# nano_shield.net
KiCad netlist of a schematic drawn in EAGLE
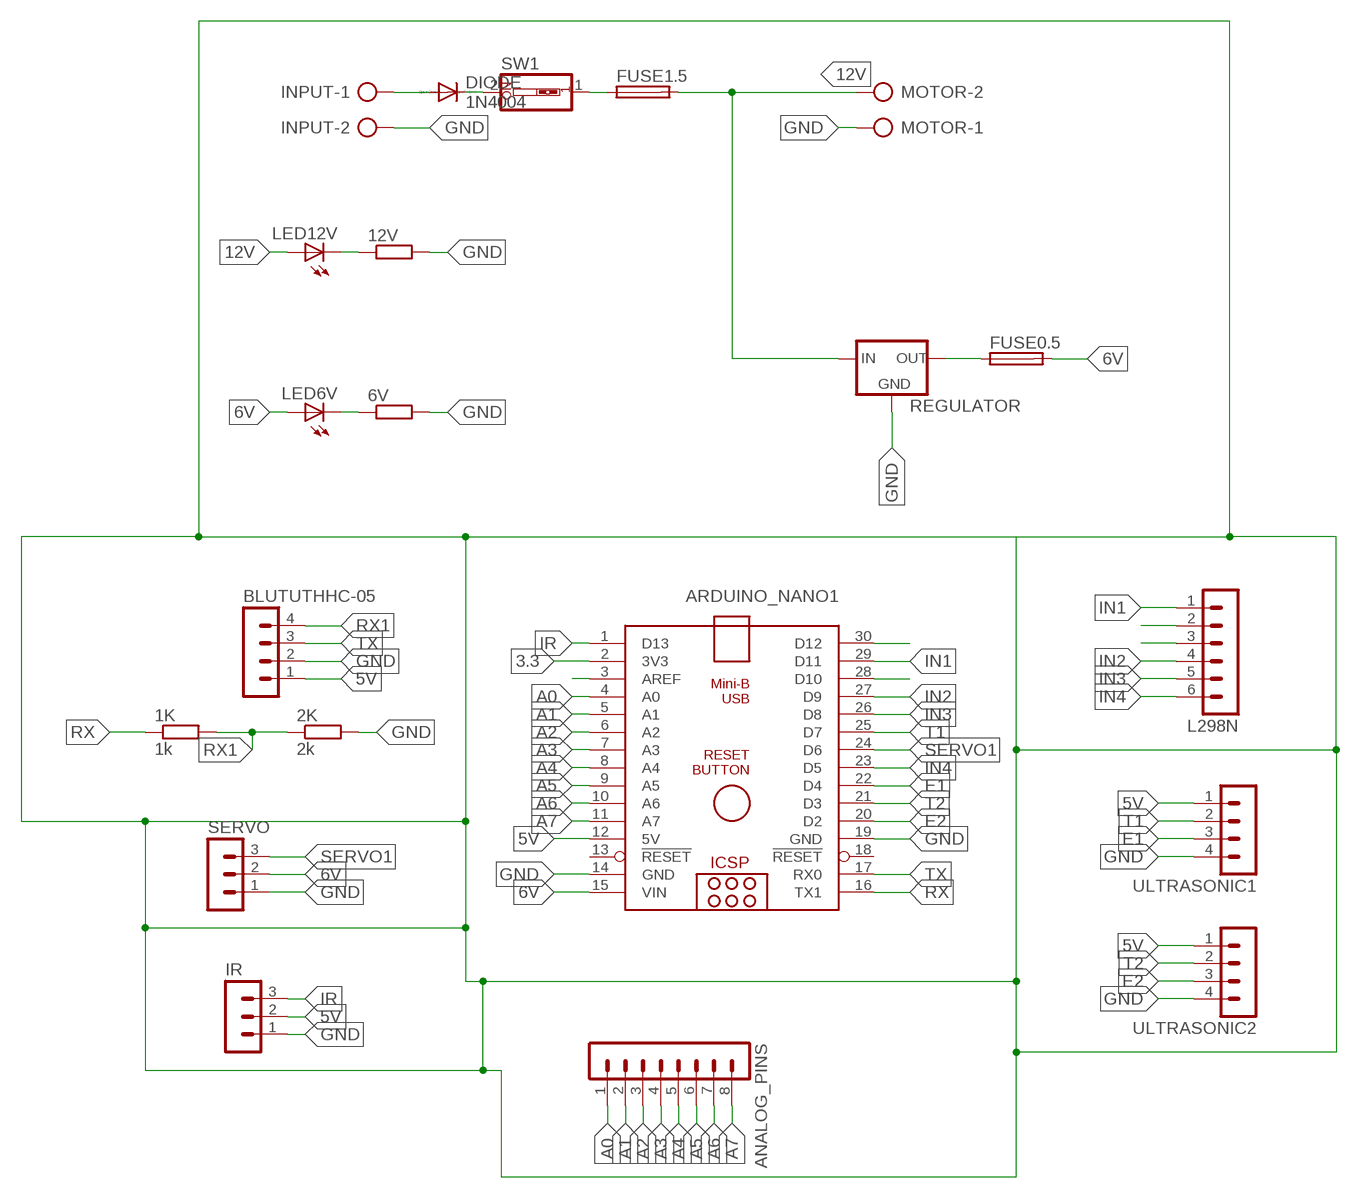
[diagram p0: schematic, sheet 1]

(export (version "E")
  (design (tool "Eeschema 10.0.6"))
  (components
    (comp (ref "1K")
      (value "1k")
      (footprint "eagle-import:0207_10")
      (libsource (lib "eagle-import") (part "R-EU_0207/10"))
    )
    (comp (ref "2K")
      (value "2k")
      (footprint "eagle-import:0207_10")
      (libsource (lib "eagle-import") (part "R-EU_0207/10"))
    )
    (comp (ref "6V")
      (value "R-EU_0204/7")
      (footprint "eagle-import:0204_7")
      (libsource (lib "eagle-import") (part "resistor_348_R-EU_0204/7"))
    )
    (comp (ref "12V")
      (value "R-EU_0204/7")
      (footprint "eagle-import:0204_7")
      (libsource (lib "eagle-import") (part "resistor_348_R-EU_0204/7"))
    )
    (comp (ref "ANALOG_PINS")
      (value "MA08-1")
      (footprint "eagle-import:MA08-1")
      (libsource (lib "eagle-import") (part "MA08-1"))
    )
    (comp (ref "ARDUINO_NANO1")
      (value "ARDUINO_NANO")
      (footprint "eagle-import:ARDUINO_NANO")
      (libsource (lib "eagle-import") (part "ARDUINO_NANO"))
    )
    (comp (ref "BLUTUTHHC-05")
      (value "MA04-1")
      (footprint "eagle-import:MA04-1")
      (libsource (lib "eagle-import") (part "MA04-1"))
    )
    (comp (ref "DIODE")
      (value "1N4004")
      (footprint "eagle-import:DO41-10")
      (libsource (lib "eagle-import") (part "1N4004"))
    )
    (comp (ref "FUSE0.5")
      (value "SH22,5")
      (footprint "eagle-import:SH22,5")
      (fields (field (name "MF") "SCHURTER") (field (name "MPN") "0031.8201"))
      (libsource (lib "eagle-import") (part "SH22,5"))
    )
    (comp (ref "FUSE1.5")
      (value "SH22,5")
      (footprint "eagle-import:SH22,5")
      (fields (field (name "MF") "SCHURTER") (field (name "MPN") "0031.8201"))
      (libsource (lib "eagle-import") (part "SH22,5"))
    )
    (comp (ref "INPUT")
      (value "AK500/2-H")
      (footprint "eagle-import:AK500_2-H")
      (libsource (lib "eagle-import") (part "AK500/2-H"))
    )
    (comp (ref "IR")
      (value "MA03-1")
      (footprint "eagle-import:MA03-1")
      (libsource (lib "eagle-import") (part "MA03-1"))
    )
    (comp (ref "L298N")
      (value "MA06-1")
      (footprint "eagle-import:MA06-1")
      (libsource (lib "eagle-import") (part "MA06-1"))
    )
    (comp (ref "LED6V")
      (value "LEDLSU260")
      (footprint "eagle-import:LSU260")
      (libsource (lib "eagle-import") (part "LEDLSU260"))
    )
    (comp (ref "LED12V")
      (value "LEDLSU260")
      (footprint "eagle-import:LSU260")
      (libsource (lib "eagle-import") (part "LEDLSU260"))
    )
    (comp (ref "MOTOR")
      (value "AK500/2-H")
      (footprint "eagle-import:AK500_2-H")
      (libsource (lib "eagle-import") (part "AK500/2-H"))
    )
    (comp (ref "REGULATOR")
      (value "78XXS")
      (footprint "eagle-import:78XXS")
      (libsource (lib "eagle-import") (part "78XXS"))
    )
    (comp (ref "SERVO")
      (value "MA03-1")
      (footprint "eagle-import:MA03-1")
      (libsource (lib "eagle-import") (part "MA03-1"))
    )
    (comp (ref "SW1")
      (value "SW_DIP-1")
      (footprint "eagle-import:EDG-01")
      (libsource (lib "eagle-import") (part "SW_DIP-1"))
    )
    (comp (ref "ULTRASONIC1")
      (value "MA04-1")
      (footprint "eagle-import:MA04-1")
      (libsource (lib "eagle-import") (part "MA04-1"))
    )
    (comp (ref "ULTRASONIC2")
      (value "MA04-1")
      (footprint "eagle-import:MA04-1")
      (libsource (lib "eagle-import") (part "MA04-1"))
    )
  )
  (nets
    (net (code "1") (name "/PWM1") (class "Default")
      (node (ref "ARDUINO_NANO1") (pin "29") (pinfunction "D11_29") (pintype "bidirectional"))
      (node (ref "L298N") (pin "2") (pinfunction "2_2") (pintype "passive"))
    )
    (net (code "2") (name "/PWM2") (class "Default")
      (node (ref "ARDUINO_NANO1") (pin "28") (pinfunction "D10_28") (pintype "bidirectional"))
      (node (ref "L298N") (pin "3") (pinfunction "3_3") (pintype "passive"))
    )
    (net (code "3") (name "3.3") (class "Default")
      (node (ref "ARDUINO_NANO1") (pin "2") (pinfunction "3V3_2") (pintype "output"))
    )
    (net (code "4") (name "5V") (class "Default")
      (node (ref "ARDUINO_NANO1") (pin "12") (pinfunction "5V_12") (pintype "power_in"))
      (node (ref "BLUTUTHHC-05") (pin "1") (pinfunction "1_1") (pintype "passive"))
      (node (ref "IR") (pin "2") (pinfunction "2_2") (pintype "passive"))
      (node (ref "ULTRASONIC1") (pin "1") (pinfunction "1_1") (pintype "passive"))
      (node (ref "ULTRASONIC2") (pin "1") (pinfunction "1_1") (pintype "passive"))
    )
    (net (code "5") (name "6V") (class "Default")
      (node (ref "ARDUINO_NANO1") (pin "15") (pinfunction "VIN_15") (pintype "power_in"))
      (node (ref "FUSE0.5") (pin "2") (pinfunction "2_2") (pintype "passive"))
      (node (ref "LED6V") (pin "A") (pinfunction "A_A") (pintype "passive"))
      (node (ref "SERVO") (pin "2") (pinfunction "2_2") (pintype "passive"))
    )
    (net (code "6") (name "12V") (class "Default")
      (node (ref "FUSE1.5") (pin "2") (pinfunction "2_2") (pintype "passive"))
      (node (ref "LED12V") (pin "A") (pinfunction "A_A") (pintype "passive"))
      (node (ref "MOTOR") (pin "2") (pinfunction "KL_2") (pintype "passive"))
      (node (ref "REGULATOR") (pin "IN") (pinfunction "IN_IN") (pintype "input"))
    )
    (net (code "7") (name "A0") (class "Default")
      (node (ref "ANALOG_PINS") (pin "1") (pinfunction "1_1") (pintype "passive"))
      (node (ref "ARDUINO_NANO1") (pin "4") (pinfunction "A0_4") (pintype "bidirectional"))
    )
    (net (code "8") (name "A1") (class "Default")
      (node (ref "ANALOG_PINS") (pin "2") (pinfunction "2_2") (pintype "passive"))
      (node (ref "ARDUINO_NANO1") (pin "5") (pinfunction "A1_5") (pintype "bidirectional"))
    )
    (net (code "9") (name "A2") (class "Default")
      (node (ref "ANALOG_PINS") (pin "3") (pinfunction "3_3") (pintype "passive"))
      (node (ref "ARDUINO_NANO1") (pin "6") (pinfunction "A2_6") (pintype "bidirectional"))
    )
    (net (code "10") (name "A3") (class "Default")
      (node (ref "ANALOG_PINS") (pin "4") (pinfunction "4_4") (pintype "passive"))
      (node (ref "ARDUINO_NANO1") (pin "7") (pinfunction "A3_7") (pintype "bidirectional"))
    )
    (net (code "11") (name "A4") (class "Default")
      (node (ref "ANALOG_PINS") (pin "5") (pinfunction "5_5") (pintype "passive"))
      (node (ref "ARDUINO_NANO1") (pin "8") (pinfunction "A4_8") (pintype "bidirectional"))
    )
    (net (code "12") (name "A5") (class "Default")
      (node (ref "ANALOG_PINS") (pin "6") (pinfunction "6_6") (pintype "passive"))
      (node (ref "ARDUINO_NANO1") (pin "9") (pinfunction "A5_9") (pintype "bidirectional"))
    )
    (net (code "13") (name "A6") (class "Default")
      (node (ref "ANALOG_PINS") (pin "7") (pinfunction "7_7") (pintype "passive"))
      (node (ref "ARDUINO_NANO1") (pin "10") (pinfunction "A6_10") (pintype "bidirectional"))
    )
    (net (code "14") (name "A7") (class "Default")
      (node (ref "ANALOG_PINS") (pin "8") (pinfunction "8_8") (pintype "passive"))
      (node (ref "ARDUINO_NANO1") (pin "11") (pinfunction "A7_11") (pintype "bidirectional"))
    )
    (net (code "15") (name "E1") (class "Default")
      (node (ref "ARDUINO_NANO1") (pin "22") (pinfunction "D4_22") (pintype "bidirectional"))
      (node (ref "ULTRASONIC1") (pin "3") (pinfunction "3_3") (pintype "passive"))
    )
    (net (code "16") (name "E2") (class "Default")
      (node (ref "ARDUINO_NANO1") (pin "20") (pinfunction "D2_20") (pintype "bidirectional"))
      (node (ref "ULTRASONIC2") (pin "3") (pinfunction "3_3") (pintype "passive"))
    )
    (net (code "17") (name "GND") (class "Default")
      (node (ref "12V") (pin "2") (pinfunction "2_2") (pintype "passive"))
      (node (ref "2K") (pin "2") (pinfunction "2_2") (pintype "passive"))
      (node (ref "6V") (pin "2") (pinfunction "2_2") (pintype "passive"))
      (node (ref "ARDUINO_NANO1") (pin "14") (pinfunction "GND_14") (pintype "power_in"))
      (node (ref "ARDUINO_NANO1") (pin "19") (pinfunction "GND_19") (pintype "power_in"))
      (node (ref "BLUTUTHHC-05") (pin "2") (pinfunction "2_2") (pintype "passive"))
      (node (ref "INPUT") (pin "2") (pinfunction "KL_2") (pintype "passive"))
      (node (ref "IR") (pin "1") (pinfunction "1_1") (pintype "passive"))
      (node (ref "MOTOR") (pin "1") (pinfunction "KL_1") (pintype "passive"))
      (node (ref "REGULATOR") (pin "GND") (pinfunction "GND_GND") (pintype "input"))
      (node (ref "SERVO") (pin "1") (pinfunction "1_1") (pintype "passive"))
      (node (ref "ULTRASONIC1") (pin "4") (pinfunction "4_4") (pintype "passive"))
      (node (ref "ULTRASONIC2") (pin "4") (pinfunction "4_4") (pintype "passive"))
    )
    (net (code "18") (name "IN1") (class "Default")
      (node (ref "ARDUINO_NANO1") (pin "30") (pinfunction "D12_30") (pintype "bidirectional"))
      (node (ref "L298N") (pin "1") (pinfunction "1_1") (pintype "passive"))
    )
    (net (code "19") (name "IN2") (class "Default")
      (node (ref "ARDUINO_NANO1") (pin "27") (pinfunction "D9_27") (pintype "bidirectional"))
      (node (ref "L298N") (pin "4") (pinfunction "4_4") (pintype "passive"))
    )
    (net (code "20") (name "IN3") (class "Default")
      (node (ref "ARDUINO_NANO1") (pin "26") (pinfunction "D8_26") (pintype "bidirectional"))
      (node (ref "L298N") (pin "5") (pinfunction "5_5") (pintype "passive"))
    )
    (net (code "21") (name "IN4") (class "Default")
      (node (ref "ARDUINO_NANO1") (pin "23") (pinfunction "D5_23") (pintype "bidirectional"))
      (node (ref "L298N") (pin "6") (pinfunction "6_6") (pintype "passive"))
    )
    (net (code "22") (name "IR") (class "Default")
      (node (ref "ARDUINO_NANO1") (pin "1") (pinfunction "D13_1") (pintype "bidirectional"))
      (node (ref "IR") (pin "3") (pinfunction "3_3") (pintype "passive"))
    )
    (net (code "23") (name "Net-(DIODE-PadC)") (class "Default")
      (node (ref "DIODE") (pin "C") (pinfunction "C_C") (pintype "passive"))
      (node (ref "SW1") (pin "2") (pinfunction "2_2") (pintype "passive"))
    )
    (net (code "24") (name "Net-(FUSE0.5-Pad1)") (class "Default")
      (node (ref "FUSE0.5") (pin "1") (pinfunction "1_1") (pintype "passive"))
      (node (ref "REGULATOR") (pin "OUT") (pinfunction "OUT_OUT") (pintype "passive"))
    )
    (net (code "25") (name "Net-(FUSE1.5-Pad1)") (class "Default")
      (node (ref "FUSE1.5") (pin "1") (pinfunction "1_1") (pintype "passive"))
      (node (ref "SW1") (pin "1") (pinfunction "1_1") (pintype "passive"))
    )
    (net (code "26") (name "Net-(INPUTA-KL)") (class "Default")
      (node (ref "DIODE") (pin "A") (pinfunction "A_A") (pintype "passive"))
      (node (ref "INPUT") (pin "1") (pinfunction "KL_1") (pintype "passive"))
    )
    (net (code "27") (name "Net-(LED6V-C)") (class "Default")
      (node (ref "6V") (pin "1") (pinfunction "1_1") (pintype "passive"))
      (node (ref "LED6V") (pin "K") (pinfunction "C_K") (pintype "passive"))
    )
    (net (code "28") (name "Net-(LED12V-C)") (class "Default")
      (node (ref "12V") (pin "1") (pinfunction "1_1") (pintype "passive"))
      (node (ref "LED12V") (pin "K") (pinfunction "C_K") (pintype "passive"))
    )
    (net (code "29") (name "RX") (class "Default")
      (node (ref "1K") (pin "1") (pinfunction "1_1") (pintype "passive"))
      (node (ref "ARDUINO_NANO1") (pin "16") (pinfunction "TX1_16") (pintype "bidirectional"))
    )
    (net (code "30") (name "RX1") (class "Default")
      (node (ref "1K") (pin "2") (pinfunction "2_2") (pintype "passive"))
      (node (ref "2K") (pin "1") (pinfunction "1_1") (pintype "passive"))
      (node (ref "BLUTUTHHC-05") (pin "4") (pinfunction "4_4") (pintype "passive"))
    )
    (net (code "31") (name "SERVO1") (class "Default")
      (node (ref "ARDUINO_NANO1") (pin "24") (pinfunction "D6_24") (pintype "bidirectional"))
      (node (ref "SERVO") (pin "3") (pinfunction "3_3") (pintype "passive"))
    )
    (net (code "32") (name "T1") (class "Default")
      (node (ref "ARDUINO_NANO1") (pin "25") (pinfunction "D7_25") (pintype "bidirectional"))
      (node (ref "ULTRASONIC1") (pin "2") (pinfunction "2_2") (pintype "passive"))
    )
    (net (code "33") (name "T2") (class "Default")
      (node (ref "ARDUINO_NANO1") (pin "21") (pinfunction "D3_21") (pintype "bidirectional"))
      (node (ref "ULTRASONIC2") (pin "2") (pinfunction "2_2") (pintype "passive"))
    )
    (net (code "34") (name "TX") (class "Default")
      (node (ref "ARDUINO_NANO1") (pin "17") (pinfunction "RX0_17") (pintype "bidirectional"))
      (node (ref "BLUTUTHHC-05") (pin "3") (pinfunction "3_3") (pintype "passive"))
    )
    (net (code "35") (name "unconnected-(ARDUINO_NANO1-AREF-Pad3)") (class "Default")
      (node (ref "ARDUINO_NANO1") (pin "3") (pinfunction "AREF_3") (pintype "input"))
    )
    (net (code "36") (name "unconnected-(ARDUINO_NANO1-~{RESET}-Pad13)") (class "Default")
      (node (ref "ARDUINO_NANO1") (pin "13") (pinfunction "~{RESET}_13") (pintype "input"))
    )
    (net (code "37") (name "unconnected-(ARDUINO_NANO1-~{RESET}-Pad18)") (class "Default")
      (node (ref "ARDUINO_NANO1") (pin "18") (pinfunction "~{RESET}_18") (pintype "input"))
    )
  )
)
